# oled.net
KiCad netlist of a schematic drawn in EAGLE
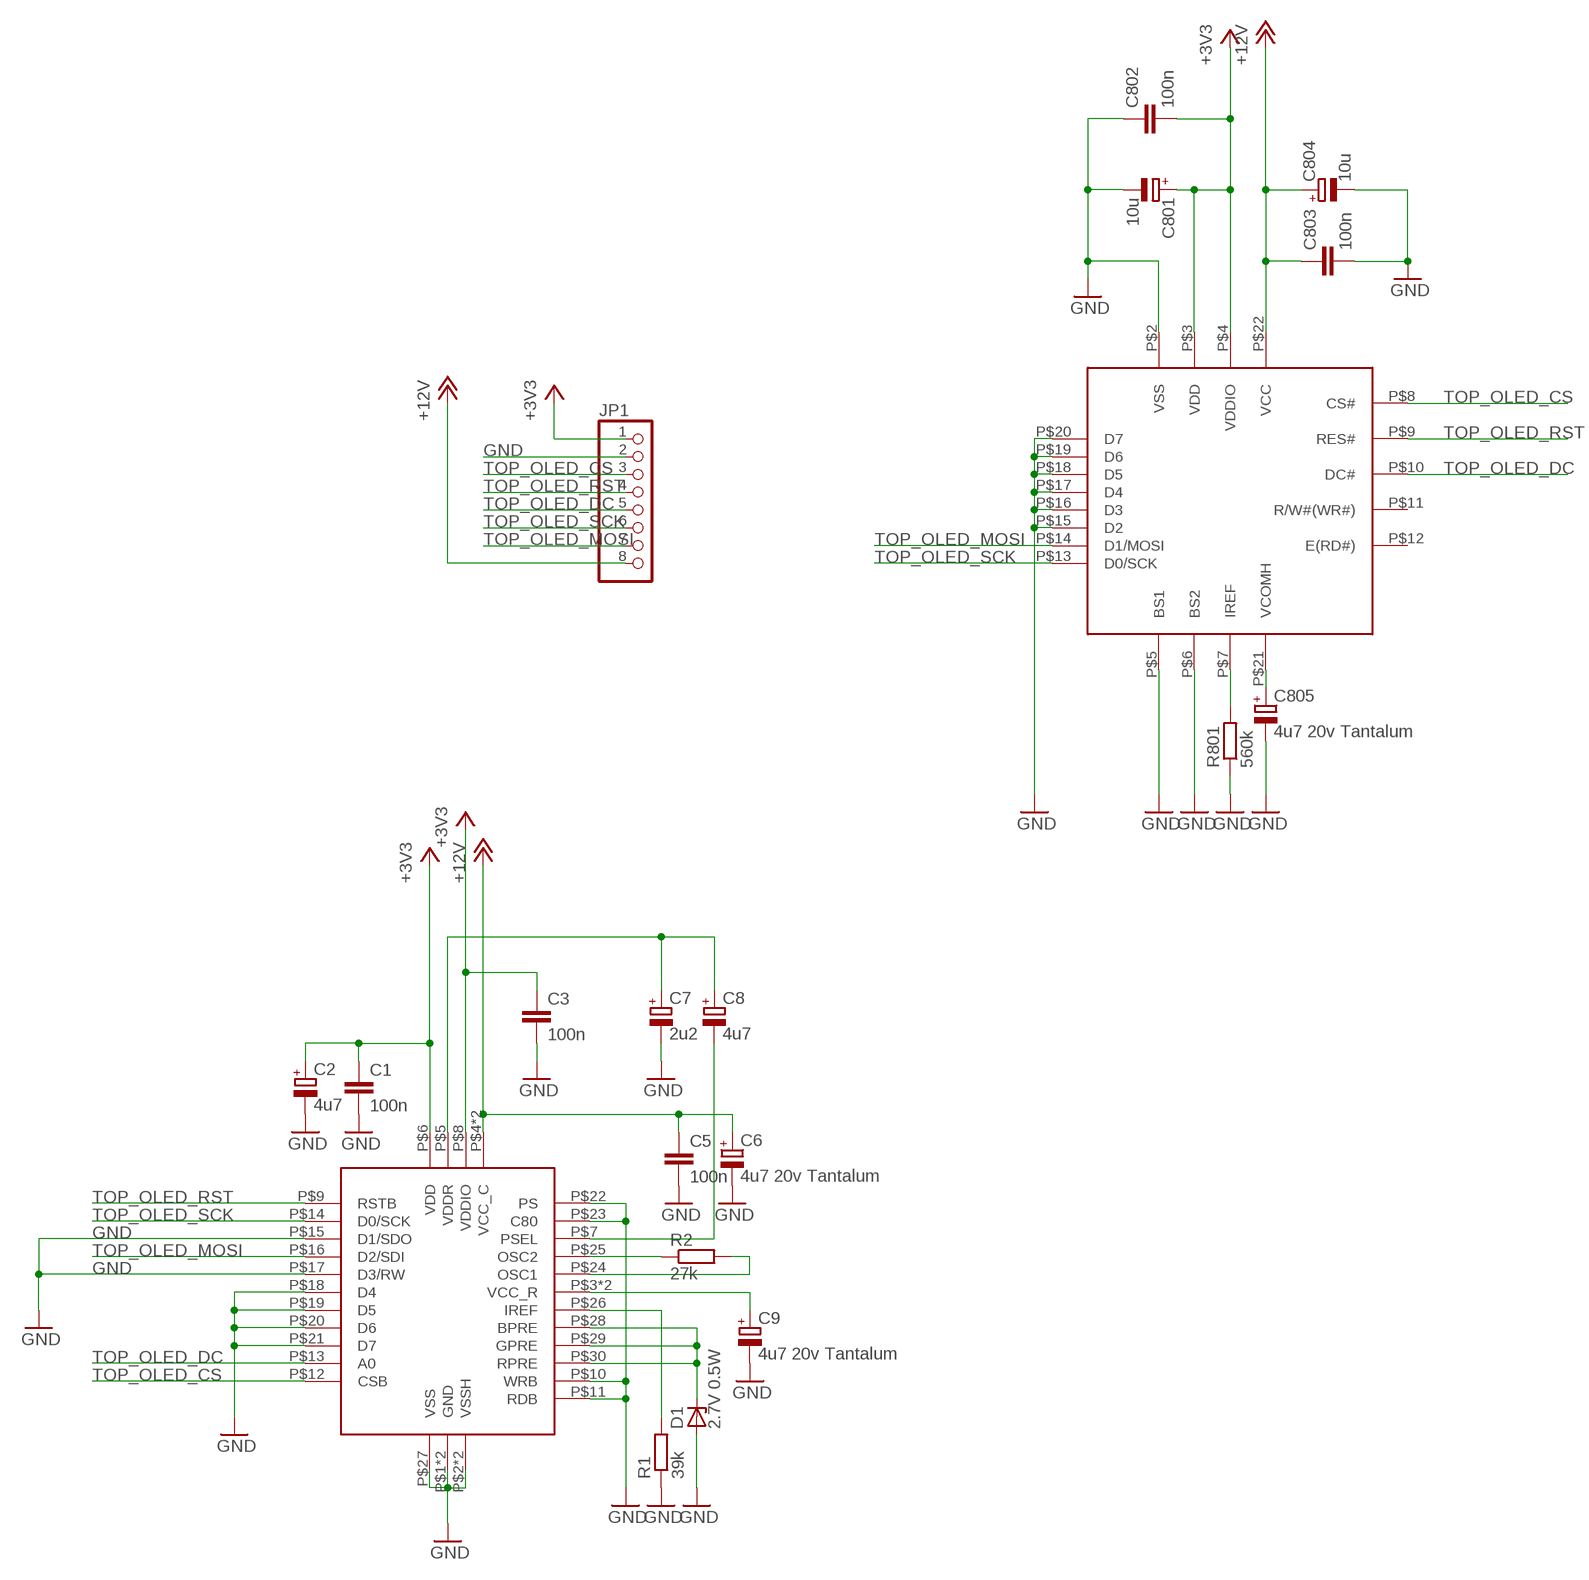
[diagram p0: schematic, sheet 1]

(export (version "E")
  (design (tool "Eeschema 10.0.6"))
  (components
    (comp (ref "C1")
      (value "100n")
      (footprint "eagle-import:C0603")
      (libsource (lib "eagle-import") (part "C-EUC0603"))
    )
    (comp (ref "C2")
      (value "4u7")
      (footprint "eagle-import:CPOL-5")
      (libsource (lib "eagle-import") (part "CPOL-EU153CLV-0505"))
    )
    (comp (ref "C3")
      (value "100n")
      (footprint "eagle-import:C0603")
      (libsource (lib "eagle-import") (part "C-EUC0603"))
    )
    (comp (ref "C5")
      (value "100n")
      (footprint "eagle-import:C0603")
      (libsource (lib "eagle-import") (part "C-EUC0603"))
    )
    (comp (ref "C6")
      (value "4u7 20v Tantalum")
      (footprint "eagle-import:CT3216")
      (libsource (lib "eagle-import") (part "CPOL-EUCT3216"))
    )
    (comp (ref "C7")
      (value "2u2")
      (footprint "eagle-import:CPOL-5")
      (libsource (lib "eagle-import") (part "CPOL-EU153CLV-0505"))
    )
    (comp (ref "C8")
      (value "4u7")
      (footprint "eagle-import:CPOL-5")
      (libsource (lib "eagle-import") (part "CPOL-EU153CLV-0505"))
    )
    (comp (ref "C9")
      (value "4u7 20v Tantalum")
      (footprint "eagle-import:CT3216")
      (libsource (lib "eagle-import") (part "CPOL-EUCT3216"))
    )
    (comp (ref "C801")
      (value "10u")
      (footprint "eagle-import:CPOL-5")
      (libsource (lib "eagle-import") (part "CPOL-EU153CLV-0505"))
    )
    (comp (ref "C802")
      (value "100n")
      (footprint "eagle-import:C0603")
      (libsource (lib "eagle-import") (part "C-EUC0603"))
    )
    (comp (ref "C803")
      (value "100n")
      (footprint "eagle-import:C0603")
      (libsource (lib "eagle-import") (part "C-EUC0603"))
    )
    (comp (ref "C804")
      (value "10u")
      (footprint "eagle-import:CPOL-5")
      (libsource (lib "eagle-import") (part "CPOL-EU153CLV-0505"))
    )
    (comp (ref "C805")
      (value "4u7 20v Tantalum")
      (footprint "eagle-import:CT3216")
      (libsource (lib "eagle-import") (part "CPOL-EUCT3216"))
    )
    (comp (ref "D1")
      (value "2.7V 0.5W")
      (footprint "eagle-import:SOD80C")
      (libsource (lib "eagle-import") (part "ZENER-DIODESOD80C"))
    )
    (comp (ref "JP1")
      (value "PINHD-1X8")
      (footprint "eagle-import:1X08")
      (libsource (lib "eagle-import") (part "PINHD-1X8"))
    )
    (comp (ref "OLED")
      (value "MCOT096064AZ-RGBM")
      (footprint "eagle-import:MCOT096064AZ-RGBM")
      (libsource (lib "eagle-import") (part "MCOT096064AZ-RGBM"))
    )
    (comp (ref "R1")
      (value "39k")
      (footprint "eagle-import:0603")
      (libsource (lib "eagle-import") (part "R-EU_0603"))
    )
    (comp (ref "R2")
      (value "27k")
      (footprint "eagle-import:0603")
      (libsource (lib "eagle-import") (part "R-EU_0603"))
    )
    (comp (ref "R801")
      (value "560k")
      (footprint "eagle-import:0603")
      (libsource (lib "eagle-import") (part "R-EU_0603"))
    )
    (comp (ref "U$1")
      (value "MCOT096096AY")
      (footprint "eagle-import:MCOT096096AY")
      (libsource (lib "eagle-import") (part "MCOT096096AY"))
    )
  )
  (nets
    (net (code "1") (name "+3V3") (class "Default")
      (node (ref "C1") (pin "1") (pinfunction "1_1") (pintype "passive"))
      (node (ref "C2") (pin "+") (pinfunction "+_+") (pintype "passive"))
      (node (ref "C3") (pin "1") (pinfunction "1_1") (pintype "passive"))
      (node (ref "C801") (pin "+") (pinfunction "+_+") (pintype "passive"))
      (node (ref "C802") (pin "2") (pinfunction "2_2") (pintype "passive"))
      (node (ref "JP1") (pin "1") (pinfunction "1_1") (pintype "passive"))
      (node (ref "OLED") (pin "P$3") (pinfunction "VDD_P$3") (pintype "bidirectional"))
      (node (ref "OLED") (pin "P$4") (pinfunction "VDDIO_P$4") (pintype "bidirectional"))
      (node (ref "U$1") (pin "P$6") (pinfunction "VDD_P$6") (pintype "bidirectional"))
      (node (ref "U$1") (pin "P$8") (pinfunction "VDDIO_P$8") (pintype "bidirectional"))
    )
    (net (code "2") (name "+12V") (class "Default")
      (node (ref "C5") (pin "1") (pinfunction "1_1") (pintype "passive"))
      (node (ref "C6") (pin "+") (pinfunction "+_+") (pintype "passive"))
      (node (ref "C803") (pin "1") (pinfunction "1_1") (pintype "passive"))
      (node (ref "C804") (pin "+") (pinfunction "+_+") (pintype "passive"))
      (node (ref "JP1") (pin "8") (pinfunction "8_8") (pintype "passive"))
      (node (ref "OLED") (pin "P$22") (pinfunction "VCC_P$22") (pintype "bidirectional"))
      (node (ref "U$1") (pin "P$31") (pinfunction "VCC_C_P$31") (pintype "bidirectional"))
      (node (ref "U$1") (pin "P$4") (pinfunction "VCC_C_P$4") (pintype "bidirectional"))
    )
    (net (code "3") (name "/TOP_OLED_CS") (class "Default")
      (node (ref "JP1") (pin "3") (pinfunction "3_3") (pintype "passive"))
      (node (ref "OLED") (pin "P$8") (pinfunction "CS#_P$8") (pintype "bidirectional"))
      (node (ref "U$1") (pin "P$12") (pinfunction "CSB_P$12") (pintype "bidirectional"))
    )
    (net (code "4") (name "/TOP_OLED_DC") (class "Default")
      (node (ref "JP1") (pin "5") (pinfunction "5_5") (pintype "passive"))
      (node (ref "OLED") (pin "P$10") (pinfunction "DC#_P$10") (pintype "bidirectional"))
      (node (ref "U$1") (pin "P$13") (pinfunction "A0_P$13") (pintype "bidirectional"))
    )
    (net (code "5") (name "/TOP_OLED_MOSI") (class "Default")
      (node (ref "JP1") (pin "7") (pinfunction "7_7") (pintype "passive"))
      (node (ref "OLED") (pin "P$14") (pinfunction "D1/MOSI_P$14") (pintype "bidirectional"))
      (node (ref "U$1") (pin "P$16") (pinfunction "D2/SDI_P$16") (pintype "bidirectional"))
    )
    (net (code "6") (name "/TOP_OLED_RST") (class "Default")
      (node (ref "JP1") (pin "4") (pinfunction "4_4") (pintype "passive"))
      (node (ref "OLED") (pin "P$9") (pinfunction "RES#_P$9") (pintype "bidirectional"))
      (node (ref "U$1") (pin "P$9") (pinfunction "RSTB_P$9") (pintype "bidirectional"))
    )
    (net (code "7") (name "/TOP_OLED_SCK") (class "Default")
      (node (ref "JP1") (pin "6") (pinfunction "6_6") (pintype "passive"))
      (node (ref "OLED") (pin "P$13") (pinfunction "D0/SCK_P$13") (pintype "bidirectional"))
      (node (ref "U$1") (pin "P$14") (pinfunction "D0/SCK_P$14") (pintype "bidirectional"))
    )
    (net (code "8") (name "GND") (class "Default")
      (node (ref "C1") (pin "2") (pinfunction "2_2") (pintype "passive"))
      (node (ref "C2") (pin "-") (pinfunction "-_-") (pintype "passive"))
      (node (ref "C3") (pin "2") (pinfunction "2_2") (pintype "passive"))
      (node (ref "C5") (pin "2") (pinfunction "2_2") (pintype "passive"))
      (node (ref "C6") (pin "-") (pinfunction "-_-") (pintype "passive"))
      (node (ref "C7") (pin "-") (pinfunction "-_-") (pintype "passive"))
      (node (ref "C801") (pin "-") (pinfunction "-_-") (pintype "passive"))
      (node (ref "C802") (pin "1") (pinfunction "1_1") (pintype "passive"))
      (node (ref "C803") (pin "2") (pinfunction "2_2") (pintype "passive"))
      (node (ref "C804") (pin "-") (pinfunction "-_-") (pintype "passive"))
      (node (ref "C805") (pin "-") (pinfunction "-_-") (pintype "passive"))
      (node (ref "C9") (pin "-") (pinfunction "-_-") (pintype "passive"))
      (node (ref "D1") (pin "A") (pinfunction "A_A") (pintype "passive"))
      (node (ref "JP1") (pin "2") (pinfunction "2_2") (pintype "passive"))
      (node (ref "OLED") (pin "P$15") (pinfunction "D2_P$15") (pintype "bidirectional"))
      (node (ref "OLED") (pin "P$16") (pinfunction "D3_P$16") (pintype "bidirectional"))
      (node (ref "OLED") (pin "P$17") (pinfunction "D4_P$17") (pintype "bidirectional"))
      (node (ref "OLED") (pin "P$18") (pinfunction "D5_P$18") (pintype "bidirectional"))
      (node (ref "OLED") (pin "P$19") (pinfunction "D6_P$19") (pintype "bidirectional"))
      (node (ref "OLED") (pin "P$2") (pinfunction "VSS_P$2") (pintype "bidirectional"))
      (node (ref "OLED") (pin "P$20") (pinfunction "D7_P$20") (pintype "bidirectional"))
      (node (ref "OLED") (pin "P$5") (pinfunction "BS1_P$5") (pintype "bidirectional"))
      (node (ref "OLED") (pin "P$6") (pinfunction "BS2_P$6") (pintype "bidirectional"))
      (node (ref "R1") (pin "1") (pinfunction "1_1") (pintype "passive"))
      (node (ref "R801") (pin "1") (pinfunction "1_1") (pintype "passive"))
      (node (ref "U$1") (pin "P$1") (pinfunction "GND_P$1") (pintype "bidirectional"))
      (node (ref "U$1") (pin "P$10") (pinfunction "WRB_P$10") (pintype "bidirectional"))
      (node (ref "U$1") (pin "P$11") (pinfunction "RDB_P$11") (pintype "bidirectional"))
      (node (ref "U$1") (pin "P$15") (pinfunction "D1/SDO_P$15") (pintype "bidirectional"))
      (node (ref "U$1") (pin "P$17") (pinfunction "D3/RW_P$17") (pintype "bidirectional"))
      (node (ref "U$1") (pin "P$18") (pinfunction "D4_P$18") (pintype "bidirectional"))
      (node (ref "U$1") (pin "P$19") (pinfunction "D5_P$19") (pintype "bidirectional"))
      (node (ref "U$1") (pin "P$2") (pinfunction "VSSH_P$2") (pintype "bidirectional"))
      (node (ref "U$1") (pin "P$20") (pinfunction "D6_P$20") (pintype "bidirectional"))
      (node (ref "U$1") (pin "P$21") (pinfunction "D7_P$21") (pintype "bidirectional"))
      (node (ref "U$1") (pin "P$22") (pinfunction "PS_P$22") (pintype "bidirectional"))
      (node (ref "U$1") (pin "P$23") (pinfunction "C80_P$23") (pintype "bidirectional"))
      (node (ref "U$1") (pin "P$27") (pinfunction "VSS_P$27") (pintype "bidirectional"))
      (node (ref "U$1") (pin "P$33") (pinfunction "VSSH_P$33") (pintype "bidirectional"))
      (node (ref "U$1") (pin "P$34") (pinfunction "GND_P$34") (pintype "bidirectional"))
    )
    (net (code "9") (name "Net-(C9-Pad+)") (class "Default")
      (node (ref "C9") (pin "+") (pinfunction "+_+") (pintype "passive"))
      (node (ref "U$1") (pin "P$3") (pinfunction "VCC_R_P$3") (pintype "bidirectional"))
      (node (ref "U$1") (pin "P$32") (pinfunction "VCC_R_P$32") (pintype "bidirectional"))
    )
    (net (code "10") (name "Net-(OLED-IREF)") (class "Default")
      (node (ref "OLED") (pin "P$7") (pinfunction "IREF_P$7") (pintype "bidirectional"))
      (node (ref "R801") (pin "2") (pinfunction "2_2") (pintype "passive"))
    )
    (net (code "11") (name "Net-(OLED-VCOMH)") (class "Default")
      (node (ref "C805") (pin "+") (pinfunction "+_+") (pintype "passive"))
      (node (ref "OLED") (pin "P$21") (pinfunction "VCOMH_P$21") (pintype "bidirectional"))
    )
    (net (code "12") (name "Net-(U$1-BPRE)") (class "Default")
      (node (ref "D1") (pin "C") (pinfunction "C_C") (pintype "passive"))
      (node (ref "U$1") (pin "P$28") (pinfunction "BPRE_P$28") (pintype "bidirectional"))
      (node (ref "U$1") (pin "P$29") (pinfunction "GPRE_P$29") (pintype "bidirectional"))
      (node (ref "U$1") (pin "P$30") (pinfunction "RPRE_P$30") (pintype "bidirectional"))
    )
    (net (code "13") (name "Net-(U$1-IREF)") (class "Default")
      (node (ref "R1") (pin "2") (pinfunction "2_2") (pintype "passive"))
      (node (ref "U$1") (pin "P$26") (pinfunction "IREF_P$26") (pintype "bidirectional"))
    )
    (net (code "14") (name "Net-(U$1-OSC1)") (class "Default")
      (node (ref "R2") (pin "2") (pinfunction "2_2") (pintype "passive"))
      (node (ref "U$1") (pin "P$24") (pinfunction "OSC1_P$24") (pintype "bidirectional"))
    )
    (net (code "15") (name "Net-(U$1-OSC2)") (class "Default")
      (node (ref "R2") (pin "1") (pinfunction "1_1") (pintype "passive"))
      (node (ref "U$1") (pin "P$25") (pinfunction "OSC2_P$25") (pintype "bidirectional"))
    )
    (net (code "16") (name "Net-(U$1-PSEL)") (class "Default")
      (node (ref "C8") (pin "-") (pinfunction "-_-") (pintype "passive"))
      (node (ref "U$1") (pin "P$7") (pinfunction "PSEL_P$7") (pintype "bidirectional"))
    )
    (net (code "17") (name "Net-(U$1-VDDR)") (class "Default")
      (node (ref "C7") (pin "+") (pinfunction "+_+") (pintype "passive"))
      (node (ref "C8") (pin "+") (pinfunction "+_+") (pintype "passive"))
      (node (ref "U$1") (pin "P$5") (pinfunction "VDDR_P$5") (pintype "bidirectional"))
    )
    (net (code "18") (name "unconnected-(OLED-E(RD#)-PadP$12)") (class "Default")
      (node (ref "OLED") (pin "P$12") (pinfunction "E(RD#)_P$12") (pintype "bidirectional"))
    )
    (net (code "19") (name "unconnected-(OLED-R{slash}W#(WR#)-PadP$11)") (class "Default")
      (node (ref "OLED") (pin "P$11") (pinfunction "R/W#(WR#)_P$11") (pintype "bidirectional"))
    )
  )
)
